# NGI_Search.net
KiCad netlist of a schematic drawn in Altium Designer
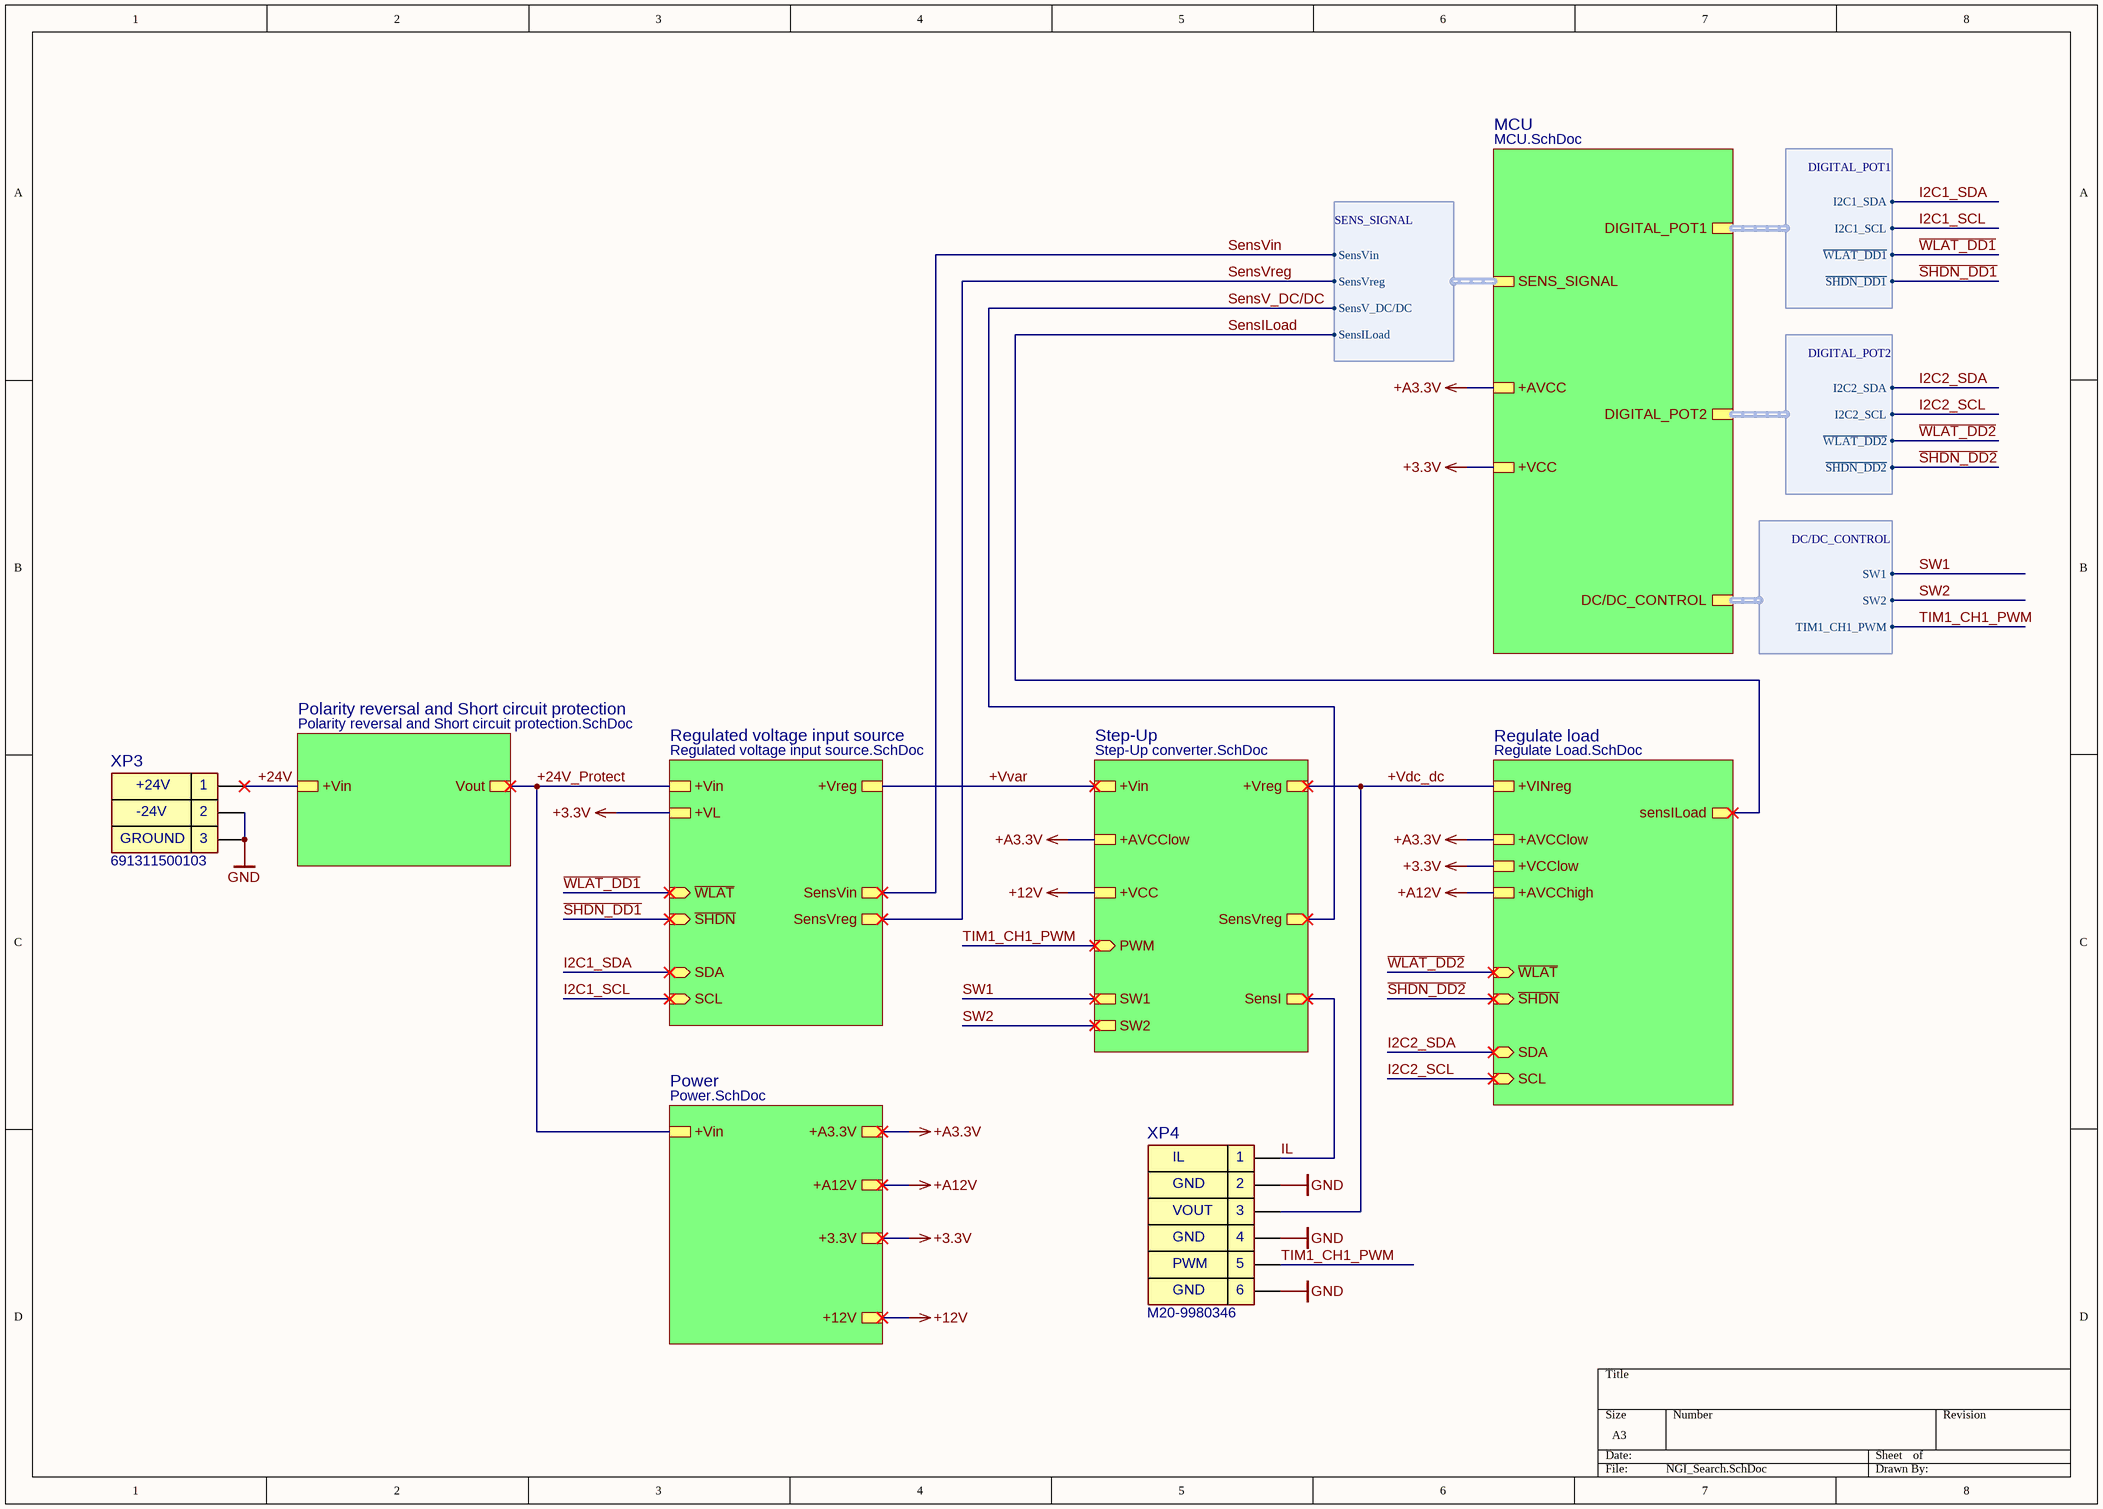
[diagram p0: NGI_Search.SchDoc]

(export (version "E")
  (design (tool "Eeschema 10.0.6"))
  (components
    (comp (ref "XP3")
      (value "691311500103")
      (footprint "691311500103")
      (description "Pluggable Terminal Blocks WR-TBL 300VAC 20A 3P Vertical")
      (fields
        (field (name "MANUFACTURER") "Wurth Elektronik")
        (field (name "MOUSER PART NUMBER") "710-691311500103")
      )
      (libsource (lib "NGI_Search") (part "691311500103"))
    )
    (comp (ref "XP4")
      (value "M20-9980346")
      (footprint "M20-9980346")
      (description "Headers & Wire Housings 03+03 DIL VERTICAL PIN HEADER TIN")
      (fields (field (name "MANUFACTURER") "Harwin") (field (name "MOUSER PART NUMBER") "855-M20-9980346"))
      (libsource (lib "NGI_Search") (part "M20-9980346"))
    )
  )
  (nets
    (net (code "9") (name "/+24V") (class "Default")
      (node (ref "XP3") (pin "1") (pintype "passive+no_connect"))
    )
    (net (code "11") (name "/+Vdc_dc") (class "Default")
      (node (ref "XP4") (pin "3") (pintype "passive+no_connect"))
    )
    (net (code "17") (name "/IL") (class "Default")
      (node (ref "XP4") (pin "1") (pintype "passive+no_connect"))
    )
    (net (code "24") (name "/TIM1_CH1_PWM") (class "Default")
      (node (ref "XP4") (pin "5") (pintype "passive+no_connect"))
    )
    (net (code "33") (name "GND") (class "Default")
      (node (ref "XP3") (pin "2") (pintype "passive"))
      (node (ref "XP3") (pin "3") (pintype "passive"))
      (node (ref "XP4") (pin "2") (pintype "passive"))
      (node (ref "XP4") (pin "4") (pintype "passive"))
      (node (ref "XP4") (pin "6") (pintype "passive"))
    )
  )
)
